# schemat_wzmacniacz_gitarowy.net
KiCad netlist of a schematic drawn in Altium Designer
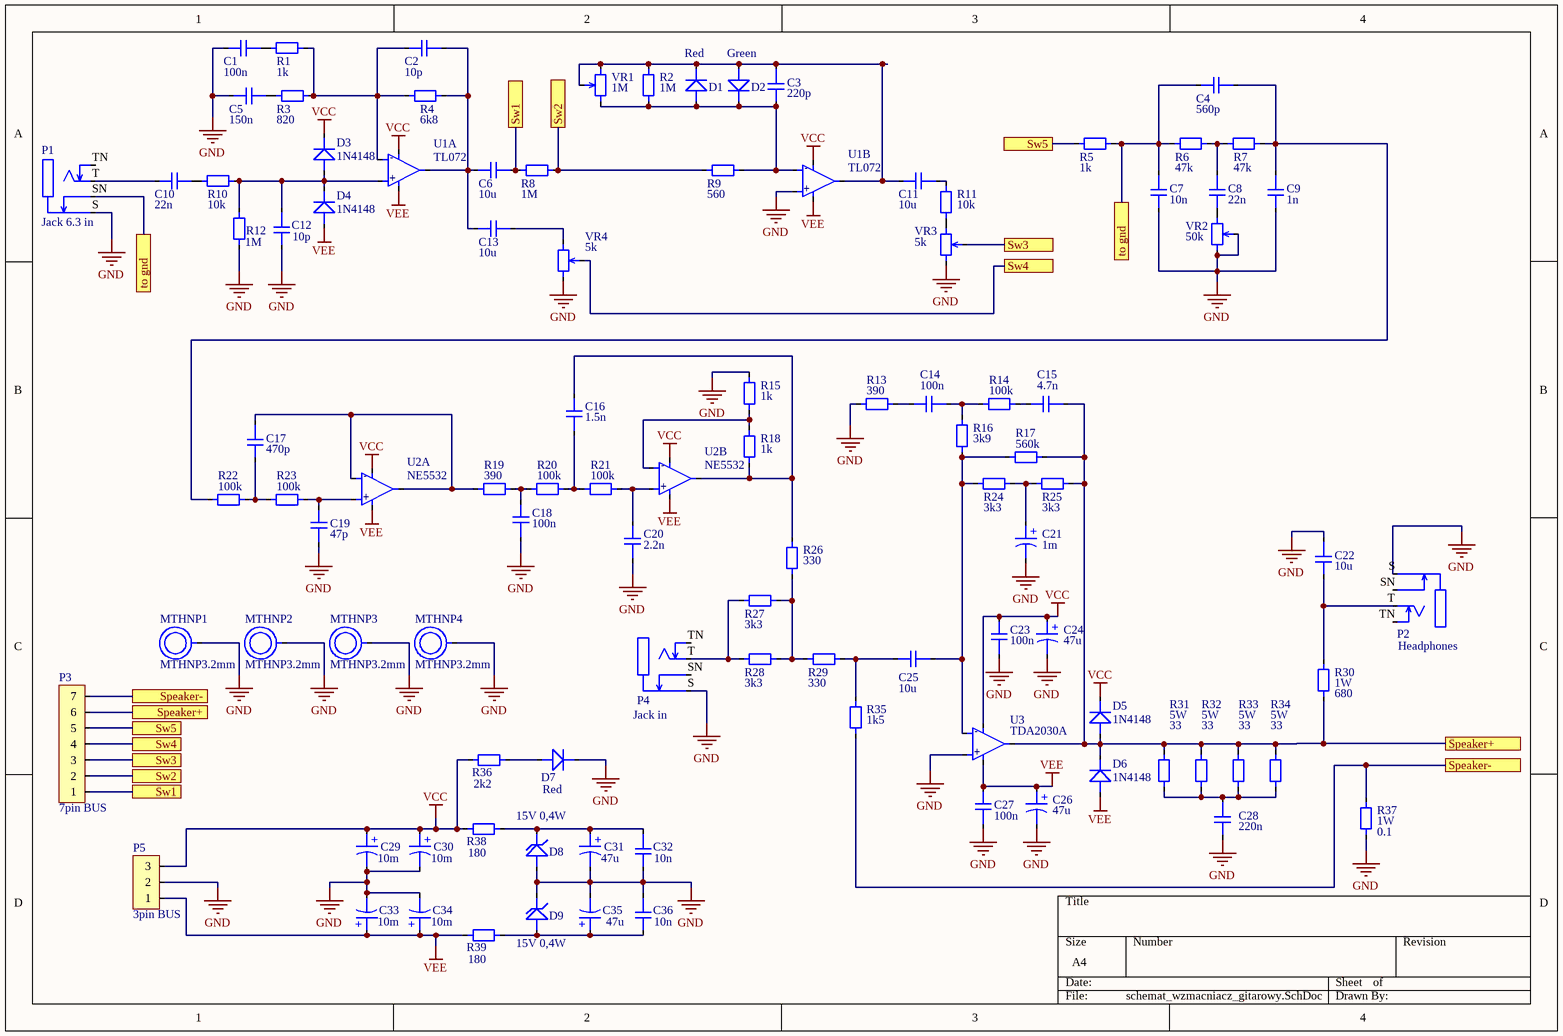
[diagram p0: schemat_wzmacniacz_gitarowy.SchDoc]

(export (version "E")
  (design (tool "Eeschema 10.0.6"))
  (components
    (comp (ref "C1")
      (value "CAP ceramic 2,5mm generic")
      (footprint "Capacitor THT 2,54mm - duplicate")
      (fields (field (name "CAPACITANCE") "100n"))
      (libsource (lib "LIB1") (part "CAP ceramic 2,5mm generic"))
    )
    (comp (ref "C2")
      (value "CAP ceramic 2,5mm generic")
      (footprint "Capacitor THT 2,54mm - duplicate")
      (fields (field (name "CAPACITANCE") "10p"))
      (libsource (lib "LIB1") (part "CAP ceramic 2,5mm generic"))
    )
    (comp (ref "C3")
      (value "CAP ceramic 2,5mm generic")
      (footprint "Capacitor THT 2,54mm - duplicate")
      (fields (field (name "CAPACITANCE") "220p"))
      (libsource (lib "LIB1") (part "CAP ceramic 2,5mm generic"))
    )
    (comp (ref "C4")
      (value "CAP ceramic 2,5mm generic")
      (footprint "Capacitor THT 2,54mm - duplicate")
      (fields (field (name "CAPACITANCE") "560p"))
      (libsource (lib "LIB1") (part "CAP ceramic 2,5mm generic"))
    )
    (comp (ref "C5")
      (value "CAP ceramic 5mm generic_1")
      (footprint "Capacitor THT 5mm")
      (fields (field (name "CAPACITANCE") "150n"))
      (libsource (lib "LIB1") (part "CAP ceramic 5mm generic_1"))
    )
    (comp (ref "C6")
      (value "CAP ceramic 2,5mm generic")
      (footprint "Capacitor THT 2,54mm - duplicate")
      (fields (field (name "CAPACITANCE") "10u"))
      (libsource (lib "LIB1") (part "CAP ceramic 2,5mm generic"))
    )
    (comp (ref "C7")
      (value "CAP ceramic 2,5mm generic")
      (footprint "Capacitor THT 2,54mm - duplicate")
      (fields (field (name "CAPACITANCE") "10n"))
      (libsource (lib "LIB1") (part "CAP ceramic 2,5mm generic"))
    )
    (comp (ref "C8")
      (value "CAP ceramic 2,5mm generic")
      (footprint "Capacitor THT 2,54mm - duplicate")
      (fields (field (name "CAPACITANCE") "22n"))
      (libsource (lib "LIB1") (part "CAP ceramic 2,5mm generic"))
    )
    (comp (ref "C9")
      (value "CAP ceramic 2,5mm generic")
      (footprint "Capacitor THT 2,54mm - duplicate")
      (fields (field (name "CAPACITANCE") "1n"))
      (libsource (lib "LIB1") (part "CAP ceramic 2,5mm generic"))
    )
    (comp (ref "C10")
      (value "CAP ceramic 2,5mm generic")
      (footprint "Capacitor THT 2,54mm - duplicate")
      (fields (field (name "CAPACITANCE") "22n"))
      (libsource (lib "LIB1") (part "CAP ceramic 2,5mm generic"))
    )
    (comp (ref "C11")
      (value "CAP ceramic 2,5mm generic")
      (footprint "Capacitor THT 2,54mm - duplicate")
      (fields (field (name "CAPACITANCE") "10u"))
      (libsource (lib "LIB1") (part "CAP ceramic 2,5mm generic"))
    )
    (comp (ref "C12")
      (value "CAP ceramic 2,5mm generic")
      (footprint "Capacitor THT 2,54mm - duplicate")
      (fields (field (name "CAPACITANCE") "10p"))
      (libsource (lib "LIB1") (part "CAP ceramic 2,5mm generic"))
    )
    (comp (ref "C13")
      (value "CAP ceramic 2,5mm generic")
      (footprint "Capacitor THT 2,54mm - duplicate")
      (fields (field (name "CAPACITANCE") "10u"))
      (libsource (lib "LIB1") (part "CAP ceramic 2,5mm generic"))
    )
    (comp (ref "C14")
      (value "CAP ceramic 2,5mm generic")
      (footprint "Capacitor THT 2,54mm - duplicate")
      (fields (field (name "CAPACITANCE") "100n"))
      (libsource (lib "LIB1") (part "CAP ceramic 2,5mm generic"))
    )
    (comp (ref "C15")
      (value "CAP ceramic 2,5mm generic")
      (footprint "Capacitor THT 2,54mm - duplicate")
      (fields (field (name "CAPACITANCE") "4.7n"))
      (libsource (lib "LIB1") (part "CAP ceramic 2,5mm generic"))
    )
    (comp (ref "C16")
      (value "CAP ceramic 2,5mm generic")
      (footprint "Capacitor THT 2,54mm - duplicate")
      (fields (field (name "CAPACITANCE") "1.5n"))
      (libsource (lib "LIB1") (part "CAP ceramic 2,5mm generic"))
    )
    (comp (ref "C17")
      (value "CAP ceramic 2,5mm generic")
      (footprint "Capacitor THT 2,54mm - duplicate")
      (fields (field (name "CAPACITANCE") "470p"))
      (libsource (lib "LIB1") (part "CAP ceramic 2,5mm generic"))
    )
    (comp (ref "C18")
      (value "CAP ceramic 2,5mm generic")
      (footprint "Capacitor THT 2,54mm - duplicate")
      (fields (field (name "CAPACITANCE") "100n"))
      (libsource (lib "LIB1") (part "CAP ceramic 2,5mm generic"))
    )
    (comp (ref "C19")
      (value "CAP ceramic 2,5mm generic")
      (footprint "Capacitor THT 2,54mm - duplicate")
      (fields (field (name "CAPACITANCE") "47p"))
      (libsource (lib "LIB1") (part "CAP ceramic 2,5mm generic"))
    )
    (comp (ref "C20")
      (value "CAP ceramic 2,5mm generic")
      (footprint "Capacitor THT 2,54mm - duplicate")
      (fields (field (name "CAPACITANCE") "2.2n"))
      (libsource (lib "LIB1") (part "CAP ceramic 2,5mm generic"))
    )
    (comp (ref "C21")
      (value "Cap electrolytic fi13 generic")
      (footprint "Capacitor Electrolytic THT fi13")
      (fields (field (name "CAPACITANCE") "1m"))
      (libsource (lib "LIB1") (part "Cap electrolytic fi13 generic"))
    )
    (comp (ref "C22")
      (value "CAP ceramic 2,5mm generic")
      (footprint "Capacitor THT 2,54mm - duplicate")
      (fields (field (name "CAPACITANCE") "10u"))
      (libsource (lib "LIB1") (part "CAP ceramic 2,5mm generic"))
    )
    (comp (ref "C23")
      (value "CAP ceramic 2,5mm generic")
      (footprint "Capacitor THT 2,54mm - duplicate")
      (fields (field (name "CAPACITANCE") "100n"))
      (libsource (lib "LIB1") (part "CAP ceramic 2,5mm generic"))
    )
    (comp (ref "C24")
      (value "Cap electrolytic fi8 generic")
      (footprint "Capacitor electrolytic tht fi8")
      (fields (field (name "CAPACITANCE") "47u"))
      (libsource (lib "LIB1") (part "Cap electrolytic fi8 generic"))
    )
    (comp (ref "C25")
      (value "CAP ceramic 2,5mm generic")
      (footprint "Capacitor THT 2,54mm - duplicate")
      (fields (field (name "CAPACITANCE") "10u"))
      (libsource (lib "LIB1") (part "CAP ceramic 2,5mm generic"))
    )
    (comp (ref "C26")
      (value "Cap electrolytic fi8 generic")
      (footprint "Capacitor electrolytic tht fi8")
      (fields (field (name "CAPACITANCE") "47u"))
      (libsource (lib "LIB1") (part "Cap electrolytic fi8 generic"))
    )
    (comp (ref "C27")
      (value "CAP ceramic 2,5mm generic")
      (footprint "Capacitor THT 2,54mm - duplicate")
      (fields (field (name "CAPACITANCE") "100n"))
      (libsource (lib "LIB1") (part "CAP ceramic 2,5mm generic"))
    )
    (comp (ref "C28")
      (value "CAP ceramic 5mm generic_1")
      (footprint "Capacitor THT 5mm")
      (fields (field (name "CAPACITANCE") "220n"))
      (libsource (lib "LIB1") (part "CAP ceramic 5mm generic_1"))
    )
    (comp (ref "C29")
      (value "Cap electrolytic fi16 generic_1")
      (footprint "Capacitor electrolytic tht fi16x40")
      (fields (field (name "CAPACITANCE") "10m"))
      (libsource (lib "LIB1") (part "Cap electrolytic fi16 generic_1"))
    )
    (comp (ref "C30")
      (value "Cap electrolytic fi16 generic_1")
      (footprint "Capacitor electrolytic tht fi16x40")
      (fields (field (name "CAPACITANCE") "10m"))
      (libsource (lib "LIB1") (part "Cap electrolytic fi16 generic_1"))
    )
    (comp (ref "C31")
      (value "Cap electrolytic fi8 generic")
      (footprint "Capacitor electrolytic tht fi8")
      (fields (field (name "CAPACITANCE") "47u"))
      (libsource (lib "LIB1") (part "Cap electrolytic fi8 generic"))
    )
    (comp (ref "C32")
      (value "CAP ceramic 2,5mm generic")
      (footprint "Capacitor THT 2,54mm - duplicate")
      (fields (field (name "CAPACITANCE") "10n"))
      (libsource (lib "LIB1") (part "CAP ceramic 2,5mm generic"))
    )
    (comp (ref "C33")
      (value "Cap electrolytic fi16 generic_1")
      (footprint "Capacitor electrolytic tht fi16x40")
      (fields (field (name "CAPACITANCE") "10m"))
      (libsource (lib "LIB1") (part "Cap electrolytic fi16 generic_1"))
    )
    (comp (ref "C34")
      (value "Cap electrolytic fi16 generic_1")
      (footprint "Capacitor electrolytic tht fi16x40")
      (fields (field (name "CAPACITANCE") "10m"))
      (libsource (lib "LIB1") (part "Cap electrolytic fi16 generic_1"))
    )
    (comp (ref "C35")
      (value "Cap electrolytic fi8 generic")
      (footprint "Capacitor electrolytic tht fi8")
      (fields (field (name "CAPACITANCE") "47u"))
      (libsource (lib "LIB1") (part "Cap electrolytic fi8 generic"))
    )
    (comp (ref "C36")
      (value "CAP ceramic 2,5mm generic")
      (footprint "Capacitor THT 2,54mm - duplicate")
      (fields (field (name "CAPACITANCE") "10n"))
      (libsource (lib "LIB1") (part "CAP ceramic 2,5mm generic"))
    )
    (comp (ref "D1")
      (value "Red")
      (footprint "Led Diode 5mm tht - duplicate")
      (libsource (lib "LIB1") (part "LED Diode"))
    )
    (comp (ref "D2")
      (value "Green")
      (footprint "Led Diode 5mm tht - duplicate")
      (libsource (lib "LIB1") (part "LED Diode"))
    )
    (comp (ref "D3") (value "1N4148") (footprint "1N4148") (libsource (lib "LIB1") (part "1N4148")))
    (comp (ref "D4") (value "1N4148") (footprint "1N4148") (libsource (lib "LIB1") (part "1N4148")))
    (comp (ref "D5") (value "1N4148") (footprint "1N4148") (libsource (lib "LIB1") (part "1N4148")))
    (comp (ref "D6") (value "1N4148") (footprint "1N4148") (libsource (lib "LIB1") (part "1N4148")))
    (comp (ref "D7")
      (value "Red")
      (footprint "Led Diode 5mm tht - duplicate")
      (libsource (lib "LIB1") (part "LED Diode"))
    )
    (comp (ref "D8")
      (value "15V 0,4W")
      (footprint "ZENER 15V 0.4W")
      (libsource (lib "LIB1") (part "Zner 15V 0,4W"))
    )
    (comp (ref "D9")
      (value "15V 0,4W")
      (footprint "ZENER 15V 0.4W")
      (libsource (lib "LIB1") (part "Zner 15V 0,4W"))
    )
    (comp (ref "MTHNP1")
      (value "MTHNP3.2mm")
      (footprint "MTH NP 3.2mm")
      (description "Mounting hole non plated 3.2mm")
      (libsource (lib "LIB1") (part "MTH NP 3.2mm"))
    )
    (comp (ref "MTHNP2")
      (value "MTHNP3.2mm")
      (footprint "MTH NP 3.2mm")
      (description "Mounting hole non plated 3.2mm")
      (libsource (lib "LIB1") (part "MTH NP 3.2mm"))
    )
    (comp (ref "MTHNP3")
      (value "MTHNP3.2mm")
      (footprint "MTH NP 3.2mm")
      (description "Mounting hole non plated 3.2mm")
      (libsource (lib "LIB1") (part "MTH NP 3.2mm"))
    )
    (comp (ref "MTHNP4")
      (value "MTHNP3.2mm")
      (footprint "MTH NP 3.2mm")
      (description "Mounting hole non plated 3.2mm")
      (libsource (lib "LIB1") (part "MTH NP 3.2mm"))
    )
    (comp (ref "P1")
      (value "Jack 6.3 in")
      (footprint "AMPHENOL ACJM-HHOP")
      (libsource (lib "LIB1") (part "AMPHENOL ACJM-HHOP"))
    )
    (comp (ref "P2")
      (value "Headphones")
      (footprint "AMPHENOL ACJM-HHOP")
      (libsource (lib "LIB1") (part "AMPHENOL ACJM-HHOP"))
    )
    (comp (ref "P3")
      (value "7pin BUS")
      (footprint "7 PIN BUS")
      (description "raster 5mm")
      (libsource (lib "LIB1") (part "7pin BUS"))
    )
    (comp (ref "P4")
      (value "Jack in")
      (footprint "AMPHENOL ACJM-HHOP")
      (libsource (lib "LIB1") (part "AMPHENOL ACJM-HHOP"))
    )
    (comp (ref "P5")
      (value "3pin BUS")
      (footprint "3 Pin BUS")
      (description "raster 5mm")
      (libsource (lib "LIB1") (part "3pin BUS"))
    )
    (comp (ref "R1")
      (value "Resistor 1/4W generic")
      (footprint "Resistor THT 0,25W")
      (fields (field (name "RESISTANCE") "1k"))
      (libsource (lib "LIB1") (part "Resistor 1/4W generic"))
    )
    (comp (ref "R2")
      (value "Resistor 1/4W generic")
      (footprint "Resistor THT 0,25W")
      (fields (field (name "RESISTANCE") "1M"))
      (libsource (lib "LIB1") (part "Resistor 1/4W generic"))
    )
    (comp (ref "R3")
      (value "Resistor 1/4W generic")
      (footprint "Resistor THT 0,25W")
      (fields (field (name "RESISTANCE") "820"))
      (libsource (lib "LIB1") (part "Resistor 1/4W generic"))
    )
    (comp (ref "R4")
      (value "Resistor 1/4W generic")
      (footprint "Resistor THT 0,25W")
      (fields (field (name "RESISTANCE") "6k8"))
      (libsource (lib "LIB1") (part "Resistor 1/4W generic"))
    )
    (comp (ref "R5")
      (value "Resistor 1/4W generic")
      (footprint "Resistor THT 0,25W")
      (fields (field (name "RESISTANCE") "1k"))
      (libsource (lib "LIB1") (part "Resistor 1/4W generic"))
    )
    (comp (ref "R6")
      (value "Resistor 1/4W generic")
      (footprint "Resistor THT 0,25W")
      (fields (field (name "RESISTANCE") "47k"))
      (libsource (lib "LIB1") (part "Resistor 1/4W generic"))
    )
    (comp (ref "R7")
      (value "Resistor 1/4W generic")
      (footprint "Resistor THT 0,25W")
      (fields (field (name "RESISTANCE") "47k"))
      (libsource (lib "LIB1") (part "Resistor 1/4W generic"))
    )
    (comp (ref "R8")
      (value "Resistor 1/4W generic")
      (footprint "Resistor THT 0,25W")
      (fields (field (name "RESISTANCE") "1M"))
      (libsource (lib "LIB1") (part "Resistor 1/4W generic"))
    )
    (comp (ref "R9")
      (value "Resistor 1/4W generic")
      (footprint "Resistor THT 0,25W")
      (fields (field (name "RESISTANCE") "560"))
      (libsource (lib "LIB1") (part "Resistor 1/4W generic"))
    )
    (comp (ref "R10")
      (value "Resistor 1/4W generic")
      (footprint "Resistor THT 0,25W")
      (fields (field (name "RESISTANCE") "10k"))
      (libsource (lib "LIB1") (part "Resistor 1/4W generic"))
    )
    (comp (ref "R11")
      (value "Resistor 1/4W generic")
      (footprint "Resistor THT 0,25W")
      (fields (field (name "RESISTANCE") "10k"))
      (libsource (lib "LIB1") (part "Resistor 1/4W generic"))
    )
    (comp (ref "R12")
      (value "Resistor 1/4W generic")
      (footprint "Resistor THT 0,25W")
      (fields (field (name "RESISTANCE") "1M"))
      (libsource (lib "LIB1") (part "Resistor 1/4W generic"))
    )
    (comp (ref "R13")
      (value "Resistor 1/4W generic")
      (footprint "Resistor THT 0,25W")
      (fields (field (name "RESISTANCE") "390"))
      (libsource (lib "LIB1") (part "Resistor 1/4W generic"))
    )
    (comp (ref "R14")
      (value "Resistor 1/4W generic")
      (footprint "Resistor THT 0,25W")
      (fields (field (name "RESISTANCE") "100k"))
      (libsource (lib "LIB1") (part "Resistor 1/4W generic"))
    )
    (comp (ref "R15")
      (value "Resistor 1/4W generic")
      (footprint "Resistor THT 0,25W")
      (fields (field (name "RESISTANCE") "1k"))
      (libsource (lib "LIB1") (part "Resistor 1/4W generic"))
    )
    (comp (ref "R16")
      (value "Resistor 1/4W generic")
      (footprint "Resistor THT 0,25W")
      (fields (field (name "RESISTANCE") "3k9"))
      (libsource (lib "LIB1") (part "Resistor 1/4W generic"))
    )
    (comp (ref "R17")
      (value "Resistor 1/4W generic")
      (footprint "Resistor THT 0,25W")
      (fields (field (name "RESISTANCE") "560k"))
      (libsource (lib "LIB1") (part "Resistor 1/4W generic"))
    )
    (comp (ref "R18")
      (value "Resistor 1/4W generic")
      (footprint "Resistor THT 0,25W")
      (fields (field (name "RESISTANCE") "1k"))
      (libsource (lib "LIB1") (part "Resistor 1/4W generic"))
    )
    (comp (ref "R19")
      (value "Resistor 1/4W generic")
      (footprint "Resistor THT 0,25W")
      (fields (field (name "RESISTANCE") "390"))
      (libsource (lib "LIB1") (part "Resistor 1/4W generic"))
    )
    (comp (ref "R20")
      (value "Resistor 1/4W generic")
      (footprint "Resistor THT 0,25W")
      (fields (field (name "RESISTANCE") "100k"))
      (libsource (lib "LIB1") (part "Resistor 1/4W generic"))
    )
    (comp (ref "R21")
      (value "Resistor 1/4W generic")
      (footprint "Resistor THT 0,25W")
      (fields (field (name "RESISTANCE") "100k"))
      (libsource (lib "LIB1") (part "Resistor 1/4W generic"))
    )
    (comp (ref "R22")
      (value "Resistor 1/4W generic")
      (footprint "Resistor THT 0,25W")
      (fields (field (name "RESISTANCE") "100k"))
      (libsource (lib "LIB1") (part "Resistor 1/4W generic"))
    )
    (comp (ref "R23")
      (value "Resistor 1/4W generic")
      (footprint "Resistor THT 0,25W")
      (fields (field (name "RESISTANCE") "100k"))
      (libsource (lib "LIB1") (part "Resistor 1/4W generic"))
    )
    (comp (ref "R24")
      (value "Resistor 1/4W generic")
      (footprint "Resistor THT 0,25W")
      (fields (field (name "RESISTANCE") "3k3"))
      (libsource (lib "LIB1") (part "Resistor 1/4W generic"))
    )
    (comp (ref "R25")
      (value "Resistor 1/4W generic")
      (footprint "Resistor THT 0,25W")
      (fields (field (name "RESISTANCE") "3k3"))
      (libsource (lib "LIB1") (part "Resistor 1/4W generic"))
    )
    (comp (ref "R26")
      (value "Resistor 1/4W generic")
      (footprint "Resistor THT 0,25W")
      (fields (field (name "RESISTANCE") "330"))
      (libsource (lib "LIB1") (part "Resistor 1/4W generic"))
    )
    (comp (ref "R27")
      (value "Resistor 1/4W generic")
      (footprint "Resistor THT 0,25W")
      (fields (field (name "RESISTANCE") "3k3"))
      (libsource (lib "LIB1") (part "Resistor 1/4W generic"))
    )
    (comp (ref "R28")
      (value "Resistor 1/4W generic")
      (footprint "Resistor THT 0,25W")
      (fields (field (name "RESISTANCE") "3k3"))
      (libsource (lib "LIB1") (part "Resistor 1/4W generic"))
    )
    (comp (ref "R29")
      (value "Resistor 1/4W generic")
      (footprint "Resistor THT 0,25W")
      (fields (field (name "RESISTANCE") "330"))
      (libsource (lib "LIB1") (part "Resistor 1/4W generic"))
    )
    (comp (ref "R30")
      (value "1W")
      (footprint "Resistor THT 1W")
      (fields (field (name "RESISTANCE") "680"))
      (libsource (lib "LIB1") (part "Resistor 1W generic"))
    )
    (comp (ref "R31")
      (value "5W")
      (footprint "Resistor THT 5W")
      (fields (field (name "RESISTANCE") "33"))
      (libsource (lib "LIB1") (part "Resistor 5W generic"))
    )
    (comp (ref "R32")
      (value "5W")
      (footprint "Resistor THT 5W")
      (fields (field (name "RESISTANCETER 1") "33"))
      (libsource (lib "LIB1") (part "Resistor 5W generic"))
    )
    (comp (ref "R33")
      (value "5W")
      (footprint "Resistor THT 5W")
      (fields (field (name "RESISTANCETER 1") "33"))
      (libsource (lib "LIB1") (part "Resistor 5W generic"))
    )
    (comp (ref "R34")
      (value "5W")
      (footprint "Resistor THT 5W")
      (fields (field (name "RESISTANCETER 1") "33"))
      (libsource (lib "LIB1") (part "Resistor 5W generic"))
    )
    (comp (ref "R35")
      (value "Resistor 1/4W generic")
      (footprint "Resistor THT 0,25W")
      (fields (field (name "RESISTANCE") "1k5"))
      (libsource (lib "LIB1") (part "Resistor 1/4W generic"))
    )
    (comp (ref "R36")
      (value "Resistor 1/4W generic")
      (footprint "Resistor THT 0,25W")
      (fields (field (name "RESISTANCE") "2k2"))
      (libsource (lib "LIB1") (part "Resistor 1/4W generic"))
    )
    (comp (ref "R37")
      (value "1W")
      (footprint "Resistor THT 1W")
      (fields (field (name "RESISTANCE") "0.1"))
      (libsource (lib "LIB1") (part "Resistor 1W generic"))
    )
    (comp (ref "R38")
      (value "Resistor 1/4W generic")
      (footprint "Resistor THT 0,25W")
      (fields (field (name "RESISTANCE") "180"))
      (libsource (lib "LIB1") (part "Resistor 1/4W generic"))
    )
    (comp (ref "R39")
      (value "Resistor 1/4W generic")
      (footprint "Resistor THT 0,25W")
      (fields (field (name "RESISTANCE") "180"))
      (libsource (lib "LIB1") (part "Resistor 1/4W generic"))
    )
    (comp (ref "U1") (value "TL072") (footprint "DIP8") (libsource (lib "LIB1") (part "TL072")))
    (comp (ref "U2") (value "NE5532") (footprint "DIP8") (libsource (lib "LIB1") (part "NE5532")))
    (comp (ref "U3") (value "TDA2030A") (footprint "TDA2030A") (libsource (lib "LIB1") (part "TDA2030A")))
    (comp (ref "VR1")
      (value "VR generic")
      (footprint "Variable Resistor")
      (fields (field (name "RESISTANCE") "1M"))
      (libsource (lib "LIB1") (part "VR generic"))
    )
    (comp (ref "VR2")
      (value "VR generic")
      (footprint "Variable Resistor")
      (fields (field (name "RESISTANCE") "50k"))
      (libsource (lib "LIB1") (part "VR generic"))
    )
    (comp (ref "VR3")
      (value "VR generic")
      (footprint "Variable Resistor")
      (fields (field (name "RESISTANCE") "5k"))
      (libsource (lib "LIB1") (part "VR generic"))
    )
    (comp (ref "VR4")
      (value "VR generic")
      (footprint "Variable Resistor")
      (fields (field (name "RESISTANCE") "5k"))
      (libsource (lib "LIB1") (part "VR generic"))
    )
  )
  (nets
    (net (code "1") (name "/Speaker+") (class "Default")
      (node (ref "C15") (pin "2") (pintype "passive"))
      (node (ref "D5") (pin "A") (pintype "passive"))
      (node (ref "D6") (pin "K") (pintype "passive"))
      (node (ref "P3") (pin "6") (pinfunction "6_6") (pintype "passive"))
      (node (ref "R17") (pin "1") (pintype "passive"))
      (node (ref "R25") (pin "1") (pintype "passive"))
      (node (ref "R30") (pin "2") (pintype "passive"))
      (node (ref "R31") (pin "1") (pintype "passive"))
      (node (ref "R32") (pin "1") (pintype "passive"))
      (node (ref "R33") (pin "1") (pintype "passive"))
      (node (ref "R34") (pin "1") (pintype "passive"))
      (node (ref "U3") (pin "4") (pinfunction "OUT_4") (pintype "passive"))
    )
    (net (code "2") (name "/Speaker-") (class "Default")
      (node (ref "P3") (pin "7") (pinfunction "7_7") (pintype "passive"))
      (node (ref "R35") (pin "1") (pintype "passive"))
      (node (ref "R37") (pin "1") (pintype "passive"))
    )
    (net (code "3") (name "/Sw1") (class "Default")
      (node (ref "C6") (pin "2") (pintype "passive"))
      (node (ref "P3") (pin "1") (pinfunction "1_1") (pintype "passive"))
      (node (ref "R8") (pin "1") (pintype "passive"))
    )
    (net (code "4") (name "/Sw2") (class "Default")
      (node (ref "P3") (pin "2") (pinfunction "2_2") (pintype "passive"))
      (node (ref "R8") (pin "2") (pintype "passive"))
      (node (ref "R9") (pin "1") (pintype "passive"))
    )
    (net (code "5") (name "/Sw3") (class "Default")
      (node (ref "P3") (pin "3") (pinfunction "3_3") (pintype "passive"))
      (node (ref "VR3") (pin "2") (pintype "passive"))
    )
    (net (code "6") (name "/Sw4") (class "Default")
      (node (ref "P3") (pin "4") (pinfunction "4_4") (pintype "passive"))
      (node (ref "VR4") (pin "2") (pintype "passive"))
    )
    (net (code "7") (name "/Sw5") (class "Default")
      (node (ref "P3") (pin "5") (pinfunction "5_5") (pintype "passive"))
      (node (ref "R5") (pin "1") (pintype "passive"))
    )
    (net (code "8") (name "/to gnd") (class "Default")
      (node (ref "C4") (pin "1") (pintype "passive"))
      (node (ref "C7") (pin "2") (pintype "passive"))
      (node (ref "P1") (pin "SN") (pintype "passive"))
      (node (ref "R5") (pin "2") (pintype "passive"))
      (node (ref "R6") (pin "1") (pintype "passive"))
    )
    (net (code "9") (name "GND") (class "Default")
      (node (ref "C1") (pin "1") (pintype "passive"))
      (node (ref "C12") (pin "1") (pintype "passive"))
      (node (ref "C18") (pin "2") (pintype "passive"))
      (node (ref "C19") (pin "2") (pintype "passive"))
      (node (ref "C20") (pin "2") (pintype "passive"))
      (node (ref "C21") (pin "2") (pintype "passive"))
      (node (ref "C22") (pin "2") (pintype "passive"))
      (node (ref "C23") (pin "2") (pintype "passive"))
      (node (ref "C24") (pin "2") (pintype "passive"))
      (node (ref "C26") (pin "2") (pintype "passive"))
      (node (ref "C27") (pin "2") (pintype "passive"))
      (node (ref "C28") (pin "1") (pintype "passive"))
      (node (ref "C29") (pin "2") (pintype "passive"))
      (node (ref "C30") (pin "2") (pintype "passive"))
      (node (ref "C31") (pin "2") (pintype "passive"))
      (node (ref "C32") (pin "1") (pintype "passive"))
      (node (ref "C33") (pin "2") (pintype "passive"))
      (node (ref "C34") (pin "2") (pintype "passive"))
      (node (ref "C35") (pin "2") (pintype "passive"))
      (node (ref "C36") (pin "2") (pintype "passive"))
      (node (ref "C5") (pin "1") (pintype "passive"))
      (node (ref "C7") (pin "1") (pintype "passive"))
      (node (ref "C9") (pin "1") (pintype "passive"))
      (node (ref "D7") (pin "K") (pintype "passive"))
      (node (ref "D8") (pin "A") (pintype "passive"))
      (node (ref "D9") (pin "K") (pintype "passive"))
      (node (ref "MTHNP1") (pin "1") (pinfunction "1_1") (pintype "passive"))
      (node (ref "MTHNP2") (pin "1") (pinfunction "1_1") (pintype "passive"))
      (node (ref "MTHNP3") (pin "1") (pinfunction "1_1") (pintype "passive"))
      (node (ref "MTHNP4") (pin "1") (pinfunction "1_1") (pintype "passive"))
      (node (ref "P1") (pin "S") (pintype "passive"))
      (node (ref "P2") (pin "S") (pintype "passive"))
      (node (ref "P4") (pin "S") (pintype "passive"))
      (node (ref "P5") (pin "2") (pinfunction "2_2") (pintype "passive"))
      (node (ref "R12") (pin "1") (pintype "passive"))
      (node (ref "R13") (pin "1") (pintype "passive"))
      (node (ref "R15") (pin "2") (pintype "passive"))
      (node (ref "R37") (pin "2") (pintype "passive"))
      (node (ref "U1") (pin "5") (pinfunction "2IN+_5") (pintype "passive"))
      (node (ref "U3") (pin "1") (pinfunction "IN+_1") (pintype "passive"))
      (node (ref "VR2") (pin "1") (pintype "passive"))
      (node (ref "VR2") (pin "2") (pintype "passive"))
      (node (ref "VR3") (pin "1") (pintype "passive"))
      (node (ref "VR4") (pin "1") (pintype "passive"))
    )
    (net (code "10") (name "Net-(C1-Pad2)") (class "Default")
      (node (ref "C1") (pin "2") (pintype "passive"))
      (node (ref "R1") (pin "1") (pintype "passive"))
    )
    (net (code "11") (name "Net-(C4-Pad2)") (class "Default")
      (node (ref "C4") (pin "2") (pintype "passive"))
      (node (ref "C9") (pin "2") (pintype "passive"))
      (node (ref "R22") (pin "1") (pintype "passive"))
      (node (ref "R7") (pin "2") (pintype "passive"))
    )
    (net (code "12") (name "Net-(C5-Pad2)") (class "Default")
      (node (ref "C5") (pin "2") (pintype "passive"))
      (node (ref "R3") (pin "1") (pintype "passive"))
    )
    (net (code "13") (name "Net-(C8-Pad1)") (class "Default")
      (node (ref "C8") (pin "1") (pintype "passive"))
      (node (ref "VR2") (pin "3") (pintype "passive"))
    )
    (net (code "14") (name "Net-(C8-Pad2)") (class "Default")
      (node (ref "C8") (pin "2") (pintype "passive"))
      (node (ref "R6") (pin "2") (pintype "passive"))
      (node (ref "R7") (pin "1") (pintype "passive"))
    )
    (net (code "15") (name "Net-(C10-Pad1)") (class "Default")
      (node (ref "C10") (pin "1") (pintype "passive"))
      (node (ref "P1") (pin "T") (pintype "passive"))
    )
    (net (code "16") (name "Net-(C10-Pad2)") (class "Default")
      (node (ref "C10") (pin "2") (pintype "passive"))
      (node (ref "R10") (pin "1") (pintype "passive"))
    )
    (net (code "17") (name "Net-(C11-Pad2)") (class "Default")
      (node (ref "C11") (pin "2") (pintype "passive"))
      (node (ref "R11") (pin "2") (pintype "passive"))
    )
    (net (code "18") (name "Net-(C13-Pad2)") (class "Default")
      (node (ref "C13") (pin "2") (pintype "passive"))
      (node (ref "VR4") (pin "3") (pintype "passive"))
    )
    (net (code "19") (name "Net-(C14-Pad1)") (class "Default")
      (node (ref "C14") (pin "1") (pintype "passive"))
      (node (ref "R13") (pin "2") (pintype "passive"))
    )
    (net (code "20") (name "Net-(C14-Pad2)") (class "Default")
      (node (ref "C14") (pin "2") (pintype "passive"))
      (node (ref "R14") (pin "1") (pintype "passive"))
      (node (ref "R16") (pin "2") (pintype "passive"))
    )
    (net (code "21") (name "Net-(C15-Pad1)") (class "Default")
      (node (ref "C15") (pin "1") (pintype "passive"))
      (node (ref "R14") (pin "2") (pintype "passive"))
    )
    (net (code "22") (name "Net-(C16-Pad2)") (class "Default")
      (node (ref "C16") (pin "2") (pintype "passive"))
      (node (ref "R20") (pin "2") (pintype "passive"))
      (node (ref "R21") (pin "1") (pintype "passive"))
    )
    (net (code "23") (name "Net-(C17-Pad1)") (class "Default")
      (node (ref "C17") (pin "1") (pintype "passive"))
      (node (ref "R22") (pin "2") (pintype "passive"))
      (node (ref "R23") (pin "1") (pintype "passive"))
    )
    (net (code "24") (name "Net-(C18-Pad1)") (class "Default")
      (node (ref "C18") (pin "1") (pintype "passive"))
      (node (ref "R19") (pin "2") (pintype "passive"))
      (node (ref "R20") (pin "1") (pintype "passive"))
    )
    (net (code "25") (name "Net-(C21-Pad1)") (class "Default")
      (node (ref "C21") (pin "1") (pintype "passive"))
      (node (ref "R24") (pin "1") (pintype "passive"))
      (node (ref "R25") (pin "2") (pintype "passive"))
    )
    (net (code "26") (name "Net-(C22-Pad1)") (class "Default")
      (node (ref "C22") (pin "1") (pintype "passive"))
      (node (ref "P2") (pin "T") (pintype "passive"))
      (node (ref "R30") (pin "1") (pintype "passive"))
    )
    (net (code "27") (name "Net-(C25-Pad1)") (class "Default")
      (node (ref "C25") (pin "1") (pintype "passive"))
      (node (ref "R29") (pin "2") (pintype "passive"))
      (node (ref "R35") (pin "2") (pintype "passive"))
    )
    (net (code "28") (name "Net-(C28-Pad2)") (class "Default")
      (node (ref "C28") (pin "2") (pintype "passive"))
      (node (ref "R31") (pin "2") (pintype "passive"))
      (node (ref "R32") (pin "2") (pintype "passive"))
      (node (ref "R33") (pin "2") (pintype "passive"))
      (node (ref "R34") (pin "2") (pintype "passive"))
    )
    (net (code "29") (name "Net-(C31-Pad1)") (class "Default")
      (node (ref "C31") (pin "1") (pintype "passive"))
      (node (ref "C32") (pin "2") (pintype "passive"))
      (node (ref "D8") (pin "K") (pintype "passive"))
      (node (ref "R38") (pin "2") (pintype "passive"))
    )
    (net (code "30") (name "Net-(C35-Pad1)") (class "Default")
      (node (ref "C35") (pin "1") (pintype "passive"))
      (node (ref "C36") (pin "1") (pintype "passive"))
      (node (ref "D9") (pin "A") (pintype "passive"))
      (node (ref "R39") (pin "2") (pintype "passive"))
    )
    (net (code "31") (name "Net-(D7-PadA)") (class "Default")
      (node (ref "D7") (pin "A") (pintype "passive"))
      (node (ref "R36") (pin "2") (pintype "passive"))
    )
    (net (code "32") (name "Net-(P4-PadT)") (class "Default")
      (node (ref "P4") (pin "T") (pintype "passive"))
      (node (ref "R27") (pin "2") (pintype "passive"))
      (node (ref "R28") (pin "1") (pintype "passive"))
    )
    (net (code "33") (name "Net-(R11-Pad1)") (class "Default")
      (node (ref "R11") (pin "1") (pintype "passive"))
      (node (ref "VR3") (pin "3") (pintype "passive"))
    )
    (net (code "34") (name "Net-(R26-Pad2)") (class "Default")
      (node (ref "R26") (pin "2") (pintype "passive"))
      (node (ref "R27") (pin "1") (pintype "passive"))
      (node (ref "R28") (pin "2") (pintype "passive"))
      (node (ref "R29") (pin "1") (pintype "passive"))
    )
    (net (code "35") (name "Net-(U1A-1IN+)") (class "Default")
      (node (ref "C12") (pin "2") (pintype "passive"))
      (node (ref "D3") (pin "A") (pintype "passive"))
      (node (ref "D4") (pin "K") (pintype "passive"))
      (node (ref "R10") (pin "2") (pintype "passive"))
      (node (ref "R12") (pin "2") (pintype "passive"))
      (node (ref "U1") (pin "3") (pinfunction "1IN+_3") (pintype "passive"))
    )
    (net (code "36") (name "Net-(U1A-1IN-)") (class "Default")
      (node (ref "C2") (pin "1") (pintype "passive"))
      (node (ref "R1") (pin "2") (pintype "passive"))
      (node (ref "R3") (pin "2") (pintype "passive"))
      (node (ref "R4") (pin "1") (pintype "passive"))
      (node (ref "U1") (pin "2") (pinfunction "1IN-_2") (pintype "passive"))
    )
    (net (code "37") (name "Net-(U1A-1OUT)") (class "Default")
      (node (ref "C13") (pin "1") (pintype "passive"))
      (node (ref "C2") (pin "2") (pintype "passive"))
      (node (ref "C6") (pin "1") (pintype "passive"))
      (node (ref "R4") (pin "2") (pintype "passive"))
      (node (ref "U1") (pin "1") (pinfunction "1OUT_1") (pintype "passive"))
    )
    (net (code "38") (name "Net-(U1B-2IN-)") (class "Default")
      (node (ref "C3") (pin "1") (pintype "passive"))
      (node (ref "D1") (pin "A") (pintype "passive"))
      (node (ref "D2") (pin "K") (pintype "passive"))
      (node (ref "R2") (pin "1") (pintype "passive"))
      (node (ref "R9") (pin "2") (pintype "passive"))
      (node (ref "U1") (pin "6") (pinfunction "2IN-_6") (pintype "passive"))
      (node (ref "VR1") (pin "3") (pintype "passive"))
    )
    (net (code "39") (name "Net-(U1B-2OUT)") (class "Default")
      (node (ref "C11") (pin "1") (pintype "passive"))
      (node (ref "C3") (pin "2") (pintype "passive"))
      (node (ref "D1") (pin "K") (pintype "passive"))
      (node (ref "D2") (pin "A") (pintype "passive"))
      (node (ref "R2") (pin "2") (pintype "passive"))
      (node (ref "U1") (pin "7") (pinfunction "2OUT_7") (pintype "passive"))
      (node (ref "VR1") (pin "1") (pintype "passive"))
      (node (ref "VR1") (pin "2") (pintype "passive"))
    )
    (net (code "40") (name "Net-(U2A-1IN+)") (class "Default")
      (node (ref "C19") (pin "1") (pintype "passive"))
      (node (ref "R23") (pin "2") (pintype "passive"))
      (node (ref "U2") (pin "3") (pinfunction "1IN+_3") (pintype "passive"))
    )
    (net (code "41") (name "Net-(U2A-1IN-)") (class "Default")
      (node (ref "C17") (pin "2") (pintype "passive"))
      (node (ref "R19") (pin "1") (pintype "passive"))
      (node (ref "U2") (pin "1") (pinfunction "1OUT_1") (pintype "passive"))
      (node (ref "U2") (pin "2") (pinfunction "1IN-_2") (pintype "passive"))
    )
    (net (code "42") (name "Net-(U2B-2IN+)") (class "Default")
      (node (ref "C20") (pin "1") (pintype "passive"))
      (node (ref "R21") (pin "2") (pintype "passive"))
      (node (ref "U2") (pin "5") (pinfunction "2IN+_5") (pintype "passive"))
    )
    (net (code "43") (name "Net-(U2B-2IN-)") (class "Default")
      (node (ref "R15") (pin "1") (pintype "passive"))
      (node (ref "R18") (pin "2") (pintype "passive"))
      (node (ref "U2") (pin "6") (pinfunction "2IN-_6") (pintype "passive"))
    )
    (net (code "44") (name "Net-(U2B-2OUT)") (class "Default")
      (node (ref "C16") (pin "1") (pintype "passive"))
      (node (ref "R18") (pin "1") (pintype "passive"))
      (node (ref "R26") (pin "1") (pintype "passive"))
      (node (ref "U2") (pin "7") (pinfunction "2OUT_7") (pintype "passive"))
    )
    (net (code "45") (name "Net-(U3-IN-)") (class "Default")
      (node (ref "C25") (pin "2") (pintype "passive"))
      (node (ref "R16") (pin "1") (pintype "passive"))
      (node (ref "R17") (pin "2") (pintype "passive"))
      (node (ref "R24") (pin "2") (pintype "passive"))
      (node (ref "U3") (pin "2") (pinfunction "IN-_2") (pintype "passive"))
    )
    (net (code "46") (name "VCC") (class "Default")
      (node (ref "C23") (pin "1") (pintype "passive"))
      (node (ref "C24") (pin "1") (pintype "passive"))
      (node (ref "C29") (pin "1") (pintype "passive"))
      (node (ref "C30") (pin "1") (pintype "passive"))
      (node (ref "D3") (pin "K") (pintype "passive"))
      (node (ref "D5") (pin "K") (pintype "passive"))
      (node (ref "P5") (pin "3") (pinfunction "3_3") (pintype "passive"))
      (node (ref "R36") (pin "1") (pintype "passive"))
      (node (ref "R38") (pin "1") (pintype "passive"))
      (node (ref "U1") (pin "8") (pinfunction "VCC_8") (pintype "passive"))
      (node (ref "U2") (pin "8") (pinfunction "VCC_8") (pintype "passive"))
      (node (ref "U3") (pin "5") (pinfunction "VCC_5") (pintype "passive"))
    )
    (net (code "47") (name "VEE") (class "Default")
      (node (ref "C26") (pin "1") (pintype "passive"))
      (node (ref "C27") (pin "1") (pintype "passive"))
      (node (ref "C33") (pin "1") (pintype "passive"))
      (node (ref "C34") (pin "1") (pintype "passive"))
      (node (ref "D4") (pin "A") (pintype "passive"))
      (node (ref "D6") (pin "A") (pintype "passive"))
      (node (ref "P5") (pin "1") (pinfunction "1_1") (pintype "passive"))
      (node (ref "R39") (pin "1") (pintype "passive"))
      (node (ref "U1") (pin "4") (pinfunction "VEE_4") (pintype "passive"))
      (node (ref "U2") (pin "4") (pinfunction "VEE_4") (pintype "passive"))
      (node (ref "U3") (pin "3") (pinfunction "VEE_3") (pintype "passive"))
    )
    (net (code "48") (name "unconnected-(P1-PadTN)") (class "Default")
      (node (ref "P1") (pin "TN") (pintype "passive"))
    )
    (net (code "49") (name "unconnected-(P2-PadSN)") (class "Default")
      (node (ref "P2") (pin "SN") (pintype "passive"))
    )
    (net (code "50") (name "unconnected-(P2-PadTN)") (class "Default")
      (node (ref "P2") (pin "TN") (pintype "passive"))
    )
    (net (code "51") (name "unconnected-(P4-PadSN)") (class "Default")
      (node (ref "P4") (pin "SN") (pintype "passive"))
    )
    (net (code "52") (name "unconnected-(P4-PadTN)") (class "Default")
      (node (ref "P4") (pin "TN") (pintype "passive"))
    )
  )
)
